# EASYEDA_SCH_WaterLevelAtmega328_2022-11-.net
KiCad netlist of a schematic drawn in EasyEDA
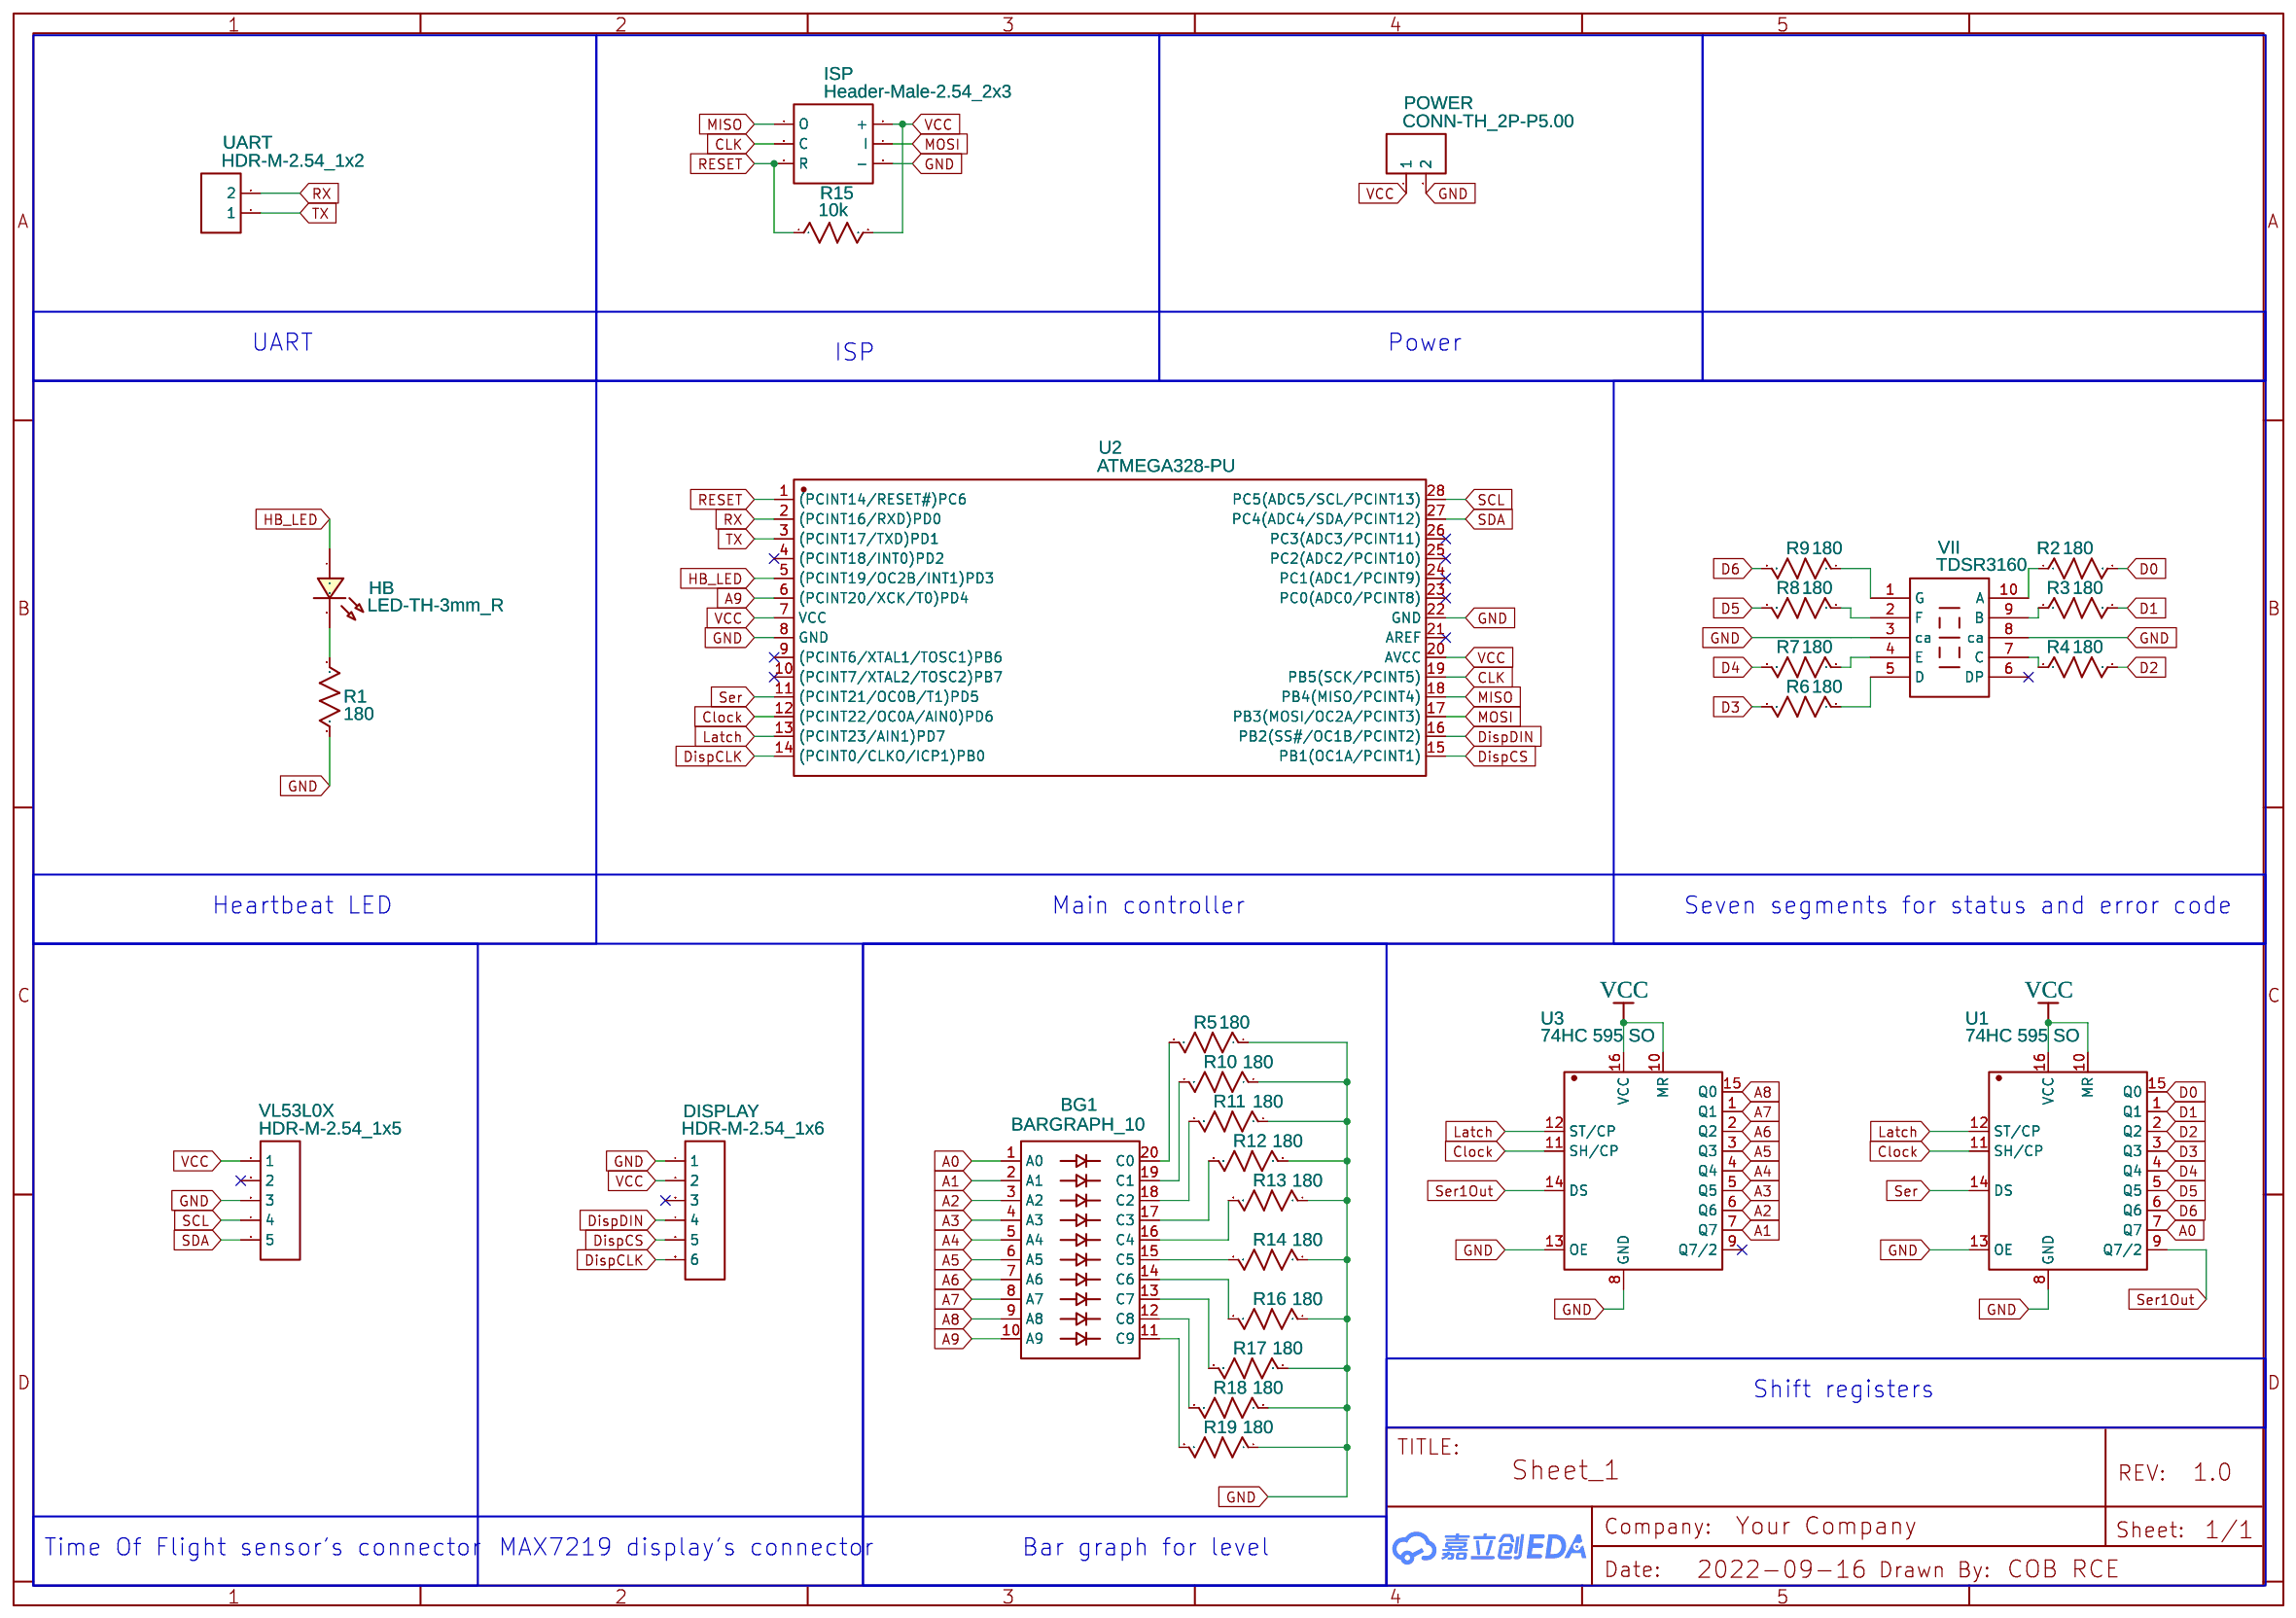
[diagram p0: schematic sheet]

(export (version "E")
  (design (tool "Eeschema 10.0.6"))
  (components
    (comp (ref "BG1") (value "BARGRAPH_10") (libsource (lib "") (part "BARGRAPH_10")))
    (comp (ref "DISPLAY")
      (value "HDR-M-2.54_1x6")
      (fields (field (name "BOM_Supplier Part") "C190819"))
      (libsource (lib "") (part "HDR-M-2.54_1x6"))
    )
    (comp (ref "HB")
      (value "LED-TH-3mm_R")
      (fields
        (field (name "BOM_Manufacturer Part") "204-10SDRD/S530-A3-L")
        (field (name "BOM_Supplier Part") "C84774")
      )
      (libsource (lib "") (part "LED-TH-3mm_R"))
    )
    (comp (ref "ISP")
      (value "Header-Male-2.54_2x3")
      (fields (field (name "BOM_Supplier Part") "C65114"))
      (libsource (lib "") (part "Unknown_415_-740"))
    )
    (comp (ref "POWER") (value "CONN-TH_2P-P5.00") (libsource (lib "") (part "CONN-TH_2P-P5.00")))
    (comp (ref "R1")
      (value "180")
      (fields (field (name "BOM_Manufacturer Part") "?"))
      (libsource (lib "") (part "Res_AXIAL-0.3(1/8W)_US_2"))
    )
    (comp (ref "R2")
      (value "180")
      (fields (field (name "BOM_Manufacturer Part") "?"))
      (libsource (lib "") (part "Res_AXIAL-0.3(1/8W)_US_1"))
    )
    (comp (ref "R3")
      (value "180")
      (fields (field (name "BOM_Manufacturer Part") "?"))
      (libsource (lib "") (part "Res_AXIAL-0.3(1/8W)_US_1"))
    )
    (comp (ref "R4")
      (value "180")
      (fields (field (name "BOM_Manufacturer Part") "?"))
      (libsource (lib "") (part "Res_AXIAL-0.3(1/8W)_US_1"))
    )
    (comp (ref "R5")
      (value "180")
      (fields (field (name "BOM_Manufacturer Part") "?"))
      (libsource (lib "") (part "Res_AXIAL-0.3(1/8W)_US"))
    )
    (comp (ref "R6")
      (value "180")
      (fields (field (name "BOM_Manufacturer Part") "?"))
      (libsource (lib "") (part "Res_AXIAL-0.3(1/8W)_US"))
    )
    (comp (ref "R7")
      (value "180")
      (fields (field (name "BOM_Manufacturer Part") "?"))
      (libsource (lib "") (part "Res_AXIAL-0.3(1/8W)_US"))
    )
    (comp (ref "R8")
      (value "180")
      (fields (field (name "BOM_Manufacturer Part") "?"))
      (libsource (lib "") (part "Res_AXIAL-0.3(1/8W)_US"))
    )
    (comp (ref "R9")
      (value "180")
      (fields (field (name "BOM_Manufacturer Part") "?"))
      (libsource (lib "") (part "Res_AXIAL-0.3(1/8W)_US"))
    )
    (comp (ref "R10")
      (value "180")
      (fields (field (name "BOM_Manufacturer Part") "?"))
      (libsource (lib "") (part "Res_AXIAL-0.3(1/8W)_US"))
    )
    (comp (ref "R11")
      (value "180")
      (fields (field (name "BOM_Manufacturer Part") "?"))
      (libsource (lib "") (part "Res_AXIAL-0.3(1/8W)_US"))
    )
    (comp (ref "R12")
      (value "180")
      (fields (field (name "BOM_Manufacturer Part") "?"))
      (libsource (lib "") (part "Res_AXIAL-0.3(1/8W)_US"))
    )
    (comp (ref "R13")
      (value "180")
      (fields (field (name "BOM_Manufacturer Part") "?"))
      (libsource (lib "") (part "Res_AXIAL-0.3(1/8W)_US"))
    )
    (comp (ref "R14")
      (value "180")
      (fields (field (name "BOM_Manufacturer Part") "?"))
      (libsource (lib "") (part "Res_AXIAL-0.3(1/8W)_US"))
    )
    (comp (ref "R15")
      (value "10k")
      (fields (field (name "BOM_Manufacturer Part") "?"))
      (libsource (lib "") (part "Res_AXIAL-0.3(1/8W)_US_1"))
    )
    (comp (ref "R16")
      (value "180")
      (fields (field (name "BOM_Manufacturer Part") "?"))
      (libsource (lib "") (part "Res_AXIAL-0.3(1/8W)_US"))
    )
    (comp (ref "R17")
      (value "180")
      (fields (field (name "BOM_Manufacturer Part") "?"))
      (libsource (lib "") (part "Res_AXIAL-0.3(1/8W)_US"))
    )
    (comp (ref "R18")
      (value "180")
      (fields (field (name "BOM_Manufacturer Part") "?"))
      (libsource (lib "") (part "Res_AXIAL-0.3(1/8W)_US"))
    )
    (comp (ref "R19")
      (value "180")
      (fields (field (name "BOM_Manufacturer Part") "?"))
      (libsource (lib "") (part "Res_AXIAL-0.3(1/8W)_US"))
    )
    (comp (ref "U1")
      (value "74HC 595 SO")
      (fields (field (name "BOM_Manufacturer Part") "74HC595A") (field (name "BOM_Supplier Part") "C110383"))
      (libsource (lib "") (part "Unknown_1040_-270"))
    )
    (comp (ref "U2")
      (value "ATMEGA328-PU")
      (fields (field (name "BOM_Supplier Part") "C613508"))
      (libsource (lib "") (part "ATMEGA328-PU"))
    )
    (comp (ref "U3")
      (value "74HC 595 SO")
      (fields (field (name "BOM_Manufacturer Part") "74HC595A") (field (name "BOM_Supplier Part") "C110383"))
      (libsource (lib "") (part "Unknown_825_-270"))
    )
    (comp (ref "UART")
      (value "HDR-M-2.54_1x2")
      (fields (field (name "BOM_Supplier Part") "C124375"))
      (libsource (lib "") (part "HDR-M-2.54_1x2"))
    )
    (comp (ref "VII") (value "TDSR3160") (libsource (lib "") (part "TDSR3160")))
    (comp (ref "VL53L0X")
      (value "HDR-M-2.54_1x5")
      (fields (field (name "BOM_Supplier Part") "C358687"))
      (libsource (lib "") (part "HDR-M-2.54_1x5"))
    )
  )
  (nets
    (net (code "1") (name "A0") (class "Default")
      (node (ref "BG1") (pin "1") (pinfunction "A0_1") (pintype "unspecified"))
      (node (ref "U1") (pin "7") (pinfunction "Q7_7") (pintype "unspecified"))
    )
    (net (code "2") (name "A1") (class "Default")
      (node (ref "BG1") (pin "2") (pinfunction "A1_2") (pintype "unspecified"))
      (node (ref "U3") (pin "7") (pinfunction "Q7_7") (pintype "unspecified"))
    )
    (net (code "3") (name "A2") (class "Default")
      (node (ref "BG1") (pin "3") (pinfunction "A2_3") (pintype "unspecified"))
      (node (ref "U3") (pin "6") (pinfunction "Q6_6") (pintype "unspecified"))
    )
    (net (code "4") (name "A3") (class "Default")
      (node (ref "BG1") (pin "4") (pinfunction "A3_4") (pintype "unspecified"))
      (node (ref "U3") (pin "5") (pinfunction "Q5_5") (pintype "unspecified"))
    )
    (net (code "5") (name "A4") (class "Default")
      (node (ref "BG1") (pin "5") (pinfunction "A4_5") (pintype "unspecified"))
      (node (ref "U3") (pin "4") (pinfunction "Q4_4") (pintype "unspecified"))
    )
    (net (code "6") (name "A5") (class "Default")
      (node (ref "BG1") (pin "6") (pinfunction "A5_6") (pintype "unspecified"))
      (node (ref "U3") (pin "3") (pinfunction "Q3_3") (pintype "unspecified"))
    )
    (net (code "7") (name "A6") (class "Default")
      (node (ref "BG1") (pin "7") (pinfunction "A6_7") (pintype "unspecified"))
      (node (ref "U3") (pin "2") (pinfunction "Q2_2") (pintype "unspecified"))
    )
    (net (code "8") (name "A7") (class "Default")
      (node (ref "BG1") (pin "8") (pinfunction "A7_8") (pintype "unspecified"))
      (node (ref "U3") (pin "1") (pinfunction "Q1_1") (pintype "unspecified"))
    )
    (net (code "9") (name "A8") (class "Default")
      (node (ref "BG1") (pin "9") (pinfunction "A8_9") (pintype "unspecified"))
      (node (ref "U3") (pin "15") (pinfunction "Q0_15") (pintype "unspecified"))
    )
    (net (code "10") (name "A9") (class "Default")
      (node (ref "BG1") (pin "10") (pinfunction "A9_10") (pintype "unspecified"))
      (node (ref "U2") (pin "6") (pinfunction "(PCINT20/XCK/T0)PD4_6") (pintype "unspecified"))
    )
    (net (code "11") (name "CLK") (class "Default")
      (node (ref "ISP") (pin "3") (pinfunction "C_3") (pintype "input"))
      (node (ref "U2") (pin "19") (pinfunction "PB5(SCK/PCINT5)_19") (pintype "unspecified"))
    )
    (net (code "12") (name "Clock") (class "Default")
      (node (ref "U1") (pin "11") (pinfunction "SH/CP_11") (pintype "unspecified"))
      (node (ref "U2") (pin "12") (pinfunction "(PCINT22/OC0A/AIN0)PD6_12") (pintype "unspecified"))
      (node (ref "U3") (pin "11") (pinfunction "SH/CP_11") (pintype "unspecified"))
    )
    (net (code "13") (name "D0") (class "Default")
      (node (ref "R2") (pin "2") (pinfunction "2_2") (pintype "unspecified"))
      (node (ref "U1") (pin "15") (pinfunction "Q0_15") (pintype "unspecified"))
    )
    (net (code "14") (name "D1") (class "Default")
      (node (ref "R3") (pin "2") (pinfunction "2_2") (pintype "unspecified"))
      (node (ref "U1") (pin "1") (pinfunction "Q1_1") (pintype "unspecified"))
    )
    (net (code "15") (name "D2") (class "Default")
      (node (ref "R4") (pin "2") (pinfunction "2_2") (pintype "unspecified"))
      (node (ref "U1") (pin "2") (pinfunction "Q2_2") (pintype "unspecified"))
    )
    (net (code "16") (name "D3") (class "Default")
      (node (ref "R6") (pin "2") (pinfunction "2_2") (pintype "unspecified"))
      (node (ref "U1") (pin "3") (pinfunction "Q3_3") (pintype "unspecified"))
    )
    (net (code "17") (name "D4") (class "Default")
      (node (ref "R7") (pin "2") (pinfunction "2_2") (pintype "unspecified"))
      (node (ref "U1") (pin "4") (pinfunction "Q4_4") (pintype "unspecified"))
    )
    (net (code "18") (name "D5") (class "Default")
      (node (ref "R8") (pin "2") (pinfunction "2_2") (pintype "unspecified"))
      (node (ref "U1") (pin "5") (pinfunction "Q5_5") (pintype "unspecified"))
    )
    (net (code "19") (name "D6") (class "Default")
      (node (ref "R9") (pin "2") (pinfunction "2_2") (pintype "unspecified"))
      (node (ref "U1") (pin "6") (pinfunction "Q6_6") (pintype "unspecified"))
    )
    (net (code "20") (name "DispCLK") (class "Default")
      (node (ref "DISPLAY") (pin "6") (pinfunction "6_6") (pintype "input"))
      (node (ref "U2") (pin "14") (pinfunction "(PCINT0/CLKO/ICP1)PB0_14") (pintype "unspecified"))
    )
    (net (code "21") (name "DispCS") (class "Default")
      (node (ref "DISPLAY") (pin "5") (pinfunction "5_5") (pintype "input"))
      (node (ref "U2") (pin "15") (pinfunction "PB1(OC1A/PCINT1)_15") (pintype "unspecified"))
    )
    (net (code "22") (name "DispDIN") (class "Default")
      (node (ref "DISPLAY") (pin "4") (pinfunction "4_4") (pintype "input"))
      (node (ref "U2") (pin "16") (pinfunction "PB2(SS#/OC1B/PCINT2)_16") (pintype "unspecified"))
    )
    (net (code "23") (name "GND") (class "Default")
      (node (ref "DISPLAY") (pin "1") (pinfunction "1_1") (pintype "input"))
      (node (ref "ISP") (pin "6") (pinfunction "-_6") (pintype "input"))
      (node (ref "POWER") (pin "2") (pinfunction "2_2") (pintype "unspecified"))
      (node (ref "R1") (pin "2") (pinfunction "2_2") (pintype "unspecified"))
      (node (ref "R10") (pin "1") (pinfunction "1_1") (pintype "unspecified"))
      (node (ref "R11") (pin "1") (pinfunction "1_1") (pintype "unspecified"))
      (node (ref "R12") (pin "1") (pinfunction "1_1") (pintype "unspecified"))
      (node (ref "R13") (pin "1") (pinfunction "1_1") (pintype "unspecified"))
      (node (ref "R14") (pin "1") (pinfunction "1_1") (pintype "unspecified"))
      (node (ref "R16") (pin "1") (pinfunction "1_1") (pintype "unspecified"))
      (node (ref "R17") (pin "1") (pinfunction "1_1") (pintype "unspecified"))
      (node (ref "R18") (pin "1") (pinfunction "1_1") (pintype "unspecified"))
      (node (ref "R19") (pin "1") (pinfunction "1_1") (pintype "unspecified"))
      (node (ref "R5") (pin "1") (pinfunction "1_1") (pintype "unspecified"))
      (node (ref "U1") (pin "13") (pinfunction "OE_13") (pintype "unspecified"))
      (node (ref "U1") (pin "8") (pinfunction "GND_8") (pintype "unspecified"))
      (node (ref "U2") (pin "22") (pinfunction "GND_22") (pintype "unspecified"))
      (node (ref "U2") (pin "8") (pinfunction "GND_8") (pintype "unspecified"))
      (node (ref "U3") (pin "13") (pinfunction "OE_13") (pintype "unspecified"))
      (node (ref "U3") (pin "8") (pinfunction "GND_8") (pintype "unspecified"))
      (node (ref "VII") (pin "3") (pinfunction "ca_3") (pintype "unspecified"))
      (node (ref "VII") (pin "8") (pinfunction "ca_8") (pintype "unspecified"))
      (node (ref "VL53L0X") (pin "3") (pinfunction "3_3") (pintype "unspecified"))
    )
    (net (code "24") (name "HB_LED") (class "Default")
      (node (ref "HB") (pin "1") (pinfunction "1_1") (pintype "unspecified"))
      (node (ref "U2") (pin "5") (pinfunction "(PCINT19/OC2B/INT1)PD3_5") (pintype "unspecified"))
    )
    (net (code "25") (name "Latch") (class "Default")
      (node (ref "U1") (pin "12") (pinfunction "ST/CP_12") (pintype "unspecified"))
      (node (ref "U2") (pin "13") (pinfunction "(PCINT23/AIN1)PD7_13") (pintype "unspecified"))
      (node (ref "U3") (pin "12") (pinfunction "ST/CP_12") (pintype "unspecified"))
    )
    (net (code "26") (name "MISO") (class "Default")
      (node (ref "ISP") (pin "1") (pinfunction "O_1") (pintype "input"))
      (node (ref "U2") (pin "18") (pinfunction "PB4(MISO/PCINT4)_18") (pintype "unspecified"))
    )
    (net (code "27") (name "MOSI") (class "Default")
      (node (ref "ISP") (pin "4") (pinfunction "I_4") (pintype "input"))
      (node (ref "U2") (pin "17") (pinfunction "PB3(MOSI/OC2A/PCINT3)_17") (pintype "unspecified"))
    )
    (net (code "28") (name "Net-(BG1-C0)") (class "Default")
      (node (ref "BG1") (pin "20") (pinfunction "C0_20") (pintype "unspecified"))
      (node (ref "R5") (pin "2") (pinfunction "2_2") (pintype "unspecified"))
    )
    (net (code "29") (name "Net-(BG1-C1)") (class "Default")
      (node (ref "BG1") (pin "19") (pinfunction "C1_19") (pintype "unspecified"))
      (node (ref "R10") (pin "2") (pinfunction "2_2") (pintype "unspecified"))
    )
    (net (code "30") (name "Net-(BG1-C2)") (class "Default")
      (node (ref "BG1") (pin "18") (pinfunction "C2_18") (pintype "unspecified"))
      (node (ref "R11") (pin "2") (pinfunction "2_2") (pintype "unspecified"))
    )
    (net (code "31") (name "Net-(BG1-C3)") (class "Default")
      (node (ref "BG1") (pin "17") (pinfunction "C3_17") (pintype "unspecified"))
      (node (ref "R12") (pin "2") (pinfunction "2_2") (pintype "unspecified"))
    )
    (net (code "32") (name "Net-(BG1-C4)") (class "Default")
      (node (ref "BG1") (pin "16") (pinfunction "C4_16") (pintype "unspecified"))
      (node (ref "R13") (pin "2") (pinfunction "2_2") (pintype "unspecified"))
    )
    (net (code "33") (name "Net-(BG1-C5)") (class "Default")
      (node (ref "BG1") (pin "15") (pinfunction "C5_15") (pintype "unspecified"))
      (node (ref "R14") (pin "2") (pinfunction "2_2") (pintype "unspecified"))
    )
    (net (code "34") (name "Net-(BG1-C6)") (class "Default")
      (node (ref "BG1") (pin "14") (pinfunction "C6_14") (pintype "unspecified"))
      (node (ref "R16") (pin "2") (pinfunction "2_2") (pintype "unspecified"))
    )
    (net (code "35") (name "Net-(BG1-C7)") (class "Default")
      (node (ref "BG1") (pin "13") (pinfunction "C7_13") (pintype "unspecified"))
      (node (ref "R17") (pin "2") (pinfunction "2_2") (pintype "unspecified"))
    )
    (net (code "36") (name "Net-(BG1-C8)") (class "Default")
      (node (ref "BG1") (pin "12") (pinfunction "C8_12") (pintype "unspecified"))
      (node (ref "R18") (pin "2") (pinfunction "2_2") (pintype "unspecified"))
    )
    (net (code "37") (name "Net-(BG1-C9)") (class "Default")
      (node (ref "BG1") (pin "11") (pinfunction "C9_11") (pintype "unspecified"))
      (node (ref "R19") (pin "2") (pinfunction "2_2") (pintype "unspecified"))
    )
    (net (code "38") (name "Net-(HB-Pad2)") (class "Default")
      (node (ref "HB") (pin "2") (pinfunction "2_2") (pintype "unspecified"))
      (node (ref "R1") (pin "1") (pinfunction "1_1") (pintype "unspecified"))
    )
    (net (code "39") (name "Net-(VII-A)") (class "Default")
      (node (ref "R2") (pin "1") (pinfunction "1_1") (pintype "unspecified"))
      (node (ref "VII") (pin "10") (pinfunction "A_10") (pintype "unspecified"))
    )
    (net (code "40") (name "Net-(VII-B)") (class "Default")
      (node (ref "R3") (pin "1") (pinfunction "1_1") (pintype "unspecified"))
      (node (ref "VII") (pin "9") (pinfunction "B_9") (pintype "unspecified"))
    )
    (net (code "41") (name "Net-(VII-C)") (class "Default")
      (node (ref "R4") (pin "1") (pinfunction "1_1") (pintype "unspecified"))
      (node (ref "VII") (pin "7") (pinfunction "C_7") (pintype "unspecified"))
    )
    (net (code "42") (name "Net-(VII-D)") (class "Default")
      (node (ref "R6") (pin "1") (pinfunction "1_1") (pintype "unspecified"))
      (node (ref "VII") (pin "5") (pinfunction "D_5") (pintype "unspecified"))
    )
    (net (code "43") (name "Net-(VII-E)") (class "Default")
      (node (ref "R7") (pin "1") (pinfunction "1_1") (pintype "unspecified"))
      (node (ref "VII") (pin "4") (pinfunction "E_4") (pintype "unspecified"))
    )
    (net (code "44") (name "Net-(VII-F)") (class "Default")
      (node (ref "R8") (pin "1") (pinfunction "1_1") (pintype "unspecified"))
      (node (ref "VII") (pin "2") (pinfunction "F_2") (pintype "unspecified"))
    )
    (net (code "45") (name "Net-(VII-G)") (class "Default")
      (node (ref "R9") (pin "1") (pinfunction "1_1") (pintype "unspecified"))
      (node (ref "VII") (pin "1") (pinfunction "G_1") (pintype "unspecified"))
    )
    (net (code "46") (name "RESET") (class "Default")
      (node (ref "ISP") (pin "5") (pinfunction "R_5") (pintype "input"))
      (node (ref "R15") (pin "1") (pinfunction "1_1") (pintype "unspecified"))
      (node (ref "U2") (pin "1") (pinfunction "(PCINT14/RESET#)PC6_1") (pintype "unspecified"))
    )
    (net (code "47") (name "RX") (class "Default")
      (node (ref "U2") (pin "2") (pinfunction "(PCINT16/RXD)PD0_2") (pintype "unspecified"))
      (node (ref "UART") (pin "2") (pinfunction "2_2") (pintype "unspecified"))
    )
    (net (code "48") (name "SCL") (class "Default")
      (node (ref "U2") (pin "28") (pinfunction "PC5(ADC5/SCL/PCINT13)_28") (pintype "unspecified"))
      (node (ref "VL53L0X") (pin "4") (pinfunction "4_4") (pintype "unspecified"))
    )
    (net (code "49") (name "SDA") (class "Default")
      (node (ref "U2") (pin "27") (pinfunction "PC4(ADC4/SDA/PCINT12)_27") (pintype "unspecified"))
      (node (ref "VL53L0X") (pin "5") (pinfunction "5_5") (pintype "unspecified"))
    )
    (net (code "50") (name "Ser") (class "Default")
      (node (ref "U1") (pin "14") (pinfunction "DS_14") (pintype "unspecified"))
      (node (ref "U2") (pin "11") (pinfunction "(PCINT21/OC0B/T1)PD5_11") (pintype "unspecified"))
    )
    (net (code "51") (name "Ser1Out") (class "Default")
      (node (ref "U1") (pin "9") (pinfunction "Q7/2_9") (pintype "unspecified"))
      (node (ref "U3") (pin "14") (pinfunction "DS_14") (pintype "unspecified"))
    )
    (net (code "52") (name "TX") (class "Default")
      (node (ref "U2") (pin "3") (pinfunction "(PCINT17/TXD)PD1_3") (pintype "unspecified"))
      (node (ref "UART") (pin "1") (pinfunction "1_1") (pintype "unspecified"))
    )
    (net (code "53") (name "VCC") (class "Default")
      (node (ref "DISPLAY") (pin "2") (pinfunction "2_2") (pintype "input"))
      (node (ref "ISP") (pin "2") (pinfunction "+_2") (pintype "input"))
      (node (ref "POWER") (pin "1") (pinfunction "1_1") (pintype "unspecified"))
      (node (ref "R15") (pin "2") (pinfunction "2_2") (pintype "unspecified"))
      (node (ref "U1") (pin "10") (pinfunction "MR_10") (pintype "unspecified"))
      (node (ref "U1") (pin "16") (pinfunction "VCC_16") (pintype "unspecified"))
      (node (ref "U2") (pin "20") (pinfunction "AVCC_20") (pintype "unspecified"))
      (node (ref "U2") (pin "7") (pinfunction "VCC_7") (pintype "unspecified"))
      (node (ref "U3") (pin "10") (pinfunction "MR_10") (pintype "unspecified"))
      (node (ref "U3") (pin "16") (pinfunction "VCC_16") (pintype "unspecified"))
      (node (ref "VL53L0X") (pin "1") (pinfunction "1_1") (pintype "unspecified"))
    )
    (net (code "54") (name "unconnected-(DISPLAY-Pad3)") (class "Default")
      (node (ref "DISPLAY") (pin "3") (pinfunction "3_3") (pintype "input+no_connect"))
    )
    (net (code "55") (name "unconnected-(U2-(PCINT6{slash}XTAL1{slash}TOSC1)PB6-Pad9)") (class "Default")
      (node (ref "U2") (pin "9") (pinfunction "(PCINT6/XTAL1/TOSC1)PB6_9") (pintype "unspecified+no_connect"))
    )
    (net (code "56") (name "unconnected-(U2-(PCINT7{slash}XTAL2{slash}TOSC2)PB7-Pad10)") (class "Default")
      (node (ref "U2") (pin "10") (pinfunction "(PCINT7/XTAL2/TOSC2)PB7_10") (pintype "unspecified+no_connect"))
    )
    (net (code "57") (name "unconnected-(U2-(PCINT18{slash}INT0)PD2-Pad4)") (class "Default")
      (node (ref "U2") (pin "4") (pinfunction "(PCINT18/INT0)PD2_4") (pintype "unspecified+no_connect"))
    )
    (net (code "58") (name "unconnected-(U2-AREF-Pad21)") (class "Default")
      (node (ref "U2") (pin "21") (pinfunction "AREF_21") (pintype "unspecified+no_connect"))
    )
    (net (code "59") (name "unconnected-(U2-PC0(ADC0{slash}PCINT8)-Pad23)") (class "Default")
      (node (ref "U2") (pin "23") (pinfunction "PC0(ADC0/PCINT8)_23") (pintype "unspecified+no_connect"))
    )
    (net (code "60") (name "unconnected-(U2-PC1(ADC1{slash}PCINT9)-Pad24)") (class "Default")
      (node (ref "U2") (pin "24") (pinfunction "PC1(ADC1/PCINT9)_24") (pintype "unspecified+no_connect"))
    )
    (net (code "61") (name "unconnected-(U2-PC2(ADC2{slash}PCINT10)-Pad25)") (class "Default")
      (node (ref "U2") (pin "25") (pinfunction "PC2(ADC2/PCINT10)_25") (pintype "unspecified+no_connect"))
    )
    (net (code "62") (name "unconnected-(U2-PC3(ADC3{slash}PCINT11)-Pad26)") (class "Default")
      (node (ref "U2") (pin "26") (pinfunction "PC3(ADC3/PCINT11)_26") (pintype "unspecified+no_connect"))
    )
    (net (code "63") (name "unconnected-(U3-Q7{slash}2-Pad9)") (class "Default")
      (node (ref "U3") (pin "9") (pinfunction "Q7/2_9") (pintype "unspecified+no_connect"))
    )
    (net (code "64") (name "unconnected-(VII-DP-Pad6)") (class "Default")
      (node (ref "VII") (pin "6") (pinfunction "DP_6") (pintype "unspecified+no_connect"))
    )
    (net (code "65") (name "unconnected-(VL53L0X-Pad2)") (class "Default")
      (node (ref "VL53L0X") (pin "2") (pinfunction "2_2") (pintype "unspecified+no_connect"))
    )
  )
)
